# GIP-CCS811.net
KiCad netlist of a schematic drawn in EAGLE
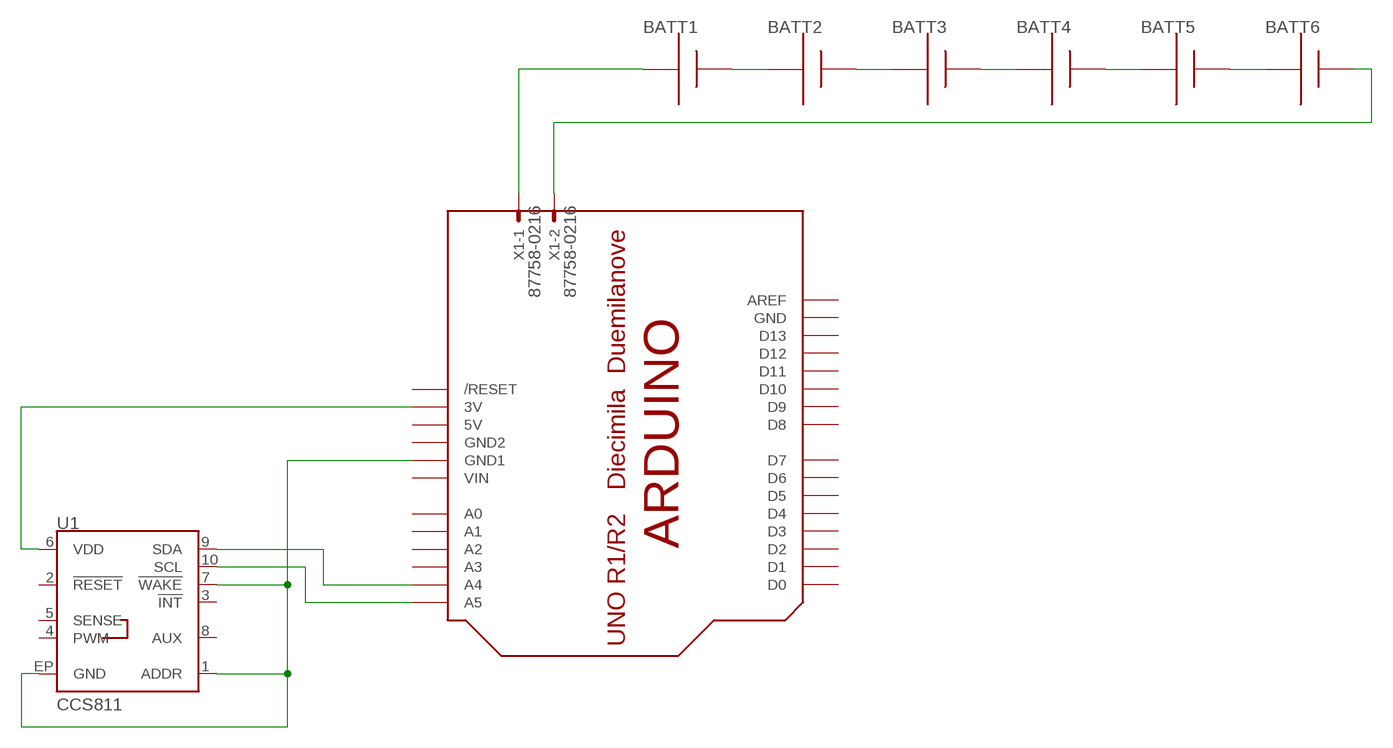
[diagram p0: schematic, sheet 1]

(export (version "E")
  (design (tool "Eeschema 10.0.6"))
  (components
    (comp (ref "BATT1")
      (value "AAA")
      (footprint "eagle-import:12BH412")
      (libsource (lib "eagle-import") (part "AAA"))
    )
    (comp (ref "BATT2")
      (value "AAA")
      (footprint "eagle-import:12BH412")
      (libsource (lib "eagle-import") (part "AAA"))
    )
    (comp (ref "BATT3")
      (value "AAA")
      (footprint "eagle-import:12BH412")
      (libsource (lib "eagle-import") (part "AAA"))
    )
    (comp (ref "BATT4")
      (value "AAA")
      (footprint "eagle-import:12BH412")
      (libsource (lib "eagle-import") (part "AAA"))
    )
    (comp (ref "BATT5")
      (value "AAA")
      (footprint "eagle-import:12BH412")
      (libsource (lib "eagle-import") (part "AAA"))
    )
    (comp (ref "BATT6")
      (value "AAA")
      (footprint "eagle-import:12BH412")
      (libsource (lib "eagle-import") (part "AAA"))
    )
    (comp (ref "U$1")
      (value "ARDUINO-BPLACE")
      (footprint "eagle-import:ARDUINO-BPLACE")
      (libsource (lib "eagle-import") (part "ARDUINO-BPLACE"))
    )
    (comp (ref "U1")
      (value "CCS811")
      (footprint "eagle-import:LGA10")
      (libsource (lib "eagle-import") (part "CCS811"))
    )
    (comp (ref "X1")
      (value "87758-0216")
      (footprint "eagle-import:87758-0216")
      (fields (field (name "MF") "MOLEX"))
      (libsource (lib "eagle-import") (part "87758-0216"))
    )
  )
  (nets
    (net (code "1") (name "/5V") (class "Default")
      (node (ref "U$1") (pin "5V") (pinfunction "5V_5V") (pintype "power_in"))
    )
    (net (code "2") (name "/GND") (class "Default")
      (node (ref "U$1") (pin "GND") (pinfunction "GND_GND") (pintype "power_in"))
    )
    (net (code "3") (name "/GND2") (class "Default")
      (node (ref "U$1") (pin "GND2") (pinfunction "GND2_GND2") (pintype "power_in"))
    )
    (net (code "4") (name "/VIN") (class "Default")
      (node (ref "U$1") (pin "VIN") (pinfunction "VIN_VIN") (pintype "power_in"))
    )
    (net (code "5") (name "Net-(BATT1-Pad+)") (class "Default")
      (node (ref "BATT1") (pin "+") (pinfunction "+_+") (pintype "bidirectional"))
      (node (ref "BATT2") (pin "-") (pinfunction "-_-") (pintype "bidirectional"))
    )
    (net (code "6") (name "Net-(BATT2-Pad+)") (class "Default")
      (node (ref "BATT2") (pin "+") (pinfunction "+_+") (pintype "bidirectional"))
      (node (ref "BATT3") (pin "-") (pinfunction "-_-") (pintype "bidirectional"))
    )
    (net (code "7") (name "Net-(BATT3-Pad+)") (class "Default")
      (node (ref "BATT3") (pin "+") (pinfunction "+_+") (pintype "bidirectional"))
      (node (ref "BATT4") (pin "-") (pinfunction "-_-") (pintype "bidirectional"))
    )
    (net (code "8") (name "Net-(BATT4-Pad+)") (class "Default")
      (node (ref "BATT4") (pin "+") (pinfunction "+_+") (pintype "bidirectional"))
      (node (ref "BATT5") (pin "-") (pinfunction "-_-") (pintype "bidirectional"))
    )
    (net (code "9") (name "Net-(BATT5-Pad+)") (class "Default")
      (node (ref "BATT5") (pin "+") (pinfunction "+_+") (pintype "bidirectional"))
      (node (ref "BATT6") (pin "-") (pinfunction "-_-") (pintype "bidirectional"))
    )
    (net (code "10") (name "Net-(U1-ADDR)") (class "Default")
      (node (ref "U$1") (pin "GND1") (pinfunction "GND1_GND1") (pintype "power_in"))
      (node (ref "U1") (pin "1") (pinfunction "ADDR_1") (pintype "bidirectional"))
      (node (ref "U1") (pin "7") (pinfunction "~{WAKE}_7") (pintype "bidirectional"))
      (node (ref "U1") (pin "EP") (pinfunction "GND_EP") (pintype "bidirectional"))
    )
    (net (code "11") (name "Net-(U1-SCL)") (class "Default")
      (node (ref "U$1") (pin "A5") (pinfunction "A5_A5") (pintype "bidirectional"))
      (node (ref "U1") (pin "10") (pinfunction "SCL_10") (pintype "bidirectional"))
    )
    (net (code "12") (name "Net-(U1-SDA)") (class "Default")
      (node (ref "U$1") (pin "A4") (pinfunction "A4_A4") (pintype "bidirectional"))
      (node (ref "U1") (pin "9") (pinfunction "SDA_9") (pintype "bidirectional"))
    )
    (net (code "13") (name "Net-(U1-VDD)") (class "Default")
      (node (ref "U$1") (pin "3V") (pinfunction "3V_3V") (pintype "power_in"))
      (node (ref "U1") (pin "6") (pinfunction "VDD_6") (pintype "bidirectional"))
    )
    (net (code "14") (name "Net-(X1A-S)") (class "Default")
      (node (ref "BATT1") (pin "-") (pinfunction "-_-") (pintype "bidirectional"))
      (node (ref "X1") (pin "1") (pinfunction "S_1") (pintype "passive"))
    )
    (net (code "15") (name "Net-(X1B-S)") (class "Default")
      (node (ref "BATT6") (pin "+") (pinfunction "+_+") (pintype "bidirectional"))
      (node (ref "X1") (pin "2") (pinfunction "S_2") (pintype "passive"))
    )
    (net (code "16") (name "unconnected-(U$1-PadA0)") (class "Default")
      (node (ref "U$1") (pin "A0") (pinfunction "A0_A0") (pintype "bidirectional"))
    )
    (net (code "17") (name "unconnected-(U$1-PadA1)") (class "Default")
      (node (ref "U$1") (pin "A1") (pinfunction "A1_A1") (pintype "bidirectional"))
    )
    (net (code "18") (name "unconnected-(U$1-PadA2)") (class "Default")
      (node (ref "U$1") (pin "A2") (pinfunction "A2_A2") (pintype "bidirectional"))
    )
    (net (code "19") (name "unconnected-(U$1-PadA3)") (class "Default")
      (node (ref "U$1") (pin "A3") (pinfunction "A3_A3") (pintype "bidirectional"))
    )
    (net (code "20") (name "unconnected-(U$1-PadAREF)") (class "Default")
      (node (ref "U$1") (pin "AREF") (pinfunction "AREF_AREF") (pintype "bidirectional"))
    )
    (net (code "21") (name "unconnected-(U$1-PadD0)") (class "Default")
      (node (ref "U$1") (pin "D0") (pinfunction "D0_D0") (pintype "bidirectional"))
    )
    (net (code "22") (name "unconnected-(U$1-PadD1)") (class "Default")
      (node (ref "U$1") (pin "D1") (pinfunction "D1_D1") (pintype "bidirectional"))
    )
    (net (code "23") (name "unconnected-(U$1-PadD2)") (class "Default")
      (node (ref "U$1") (pin "D2") (pinfunction "D2_D2") (pintype "bidirectional"))
    )
    (net (code "24") (name "unconnected-(U$1-PadD3)") (class "Default")
      (node (ref "U$1") (pin "D3") (pinfunction "D3_D3") (pintype "bidirectional"))
    )
    (net (code "25") (name "unconnected-(U$1-PadD4)") (class "Default")
      (node (ref "U$1") (pin "D4") (pinfunction "D4_D4") (pintype "bidirectional"))
    )
    (net (code "26") (name "unconnected-(U$1-PadD5)") (class "Default")
      (node (ref "U$1") (pin "D5") (pinfunction "D5_D5") (pintype "bidirectional"))
    )
    (net (code "27") (name "unconnected-(U$1-PadD6)") (class "Default")
      (node (ref "U$1") (pin "D6") (pinfunction "D6_D6") (pintype "bidirectional"))
    )
    (net (code "28") (name "unconnected-(U$1-PadD7)") (class "Default")
      (node (ref "U$1") (pin "D7") (pinfunction "D7_D7") (pintype "bidirectional"))
    )
    (net (code "29") (name "unconnected-(U$1-PadD8)") (class "Default")
      (node (ref "U$1") (pin "D8") (pinfunction "D8_D8") (pintype "bidirectional"))
    )
    (net (code "30") (name "unconnected-(U$1-PadD9)") (class "Default")
      (node (ref "U$1") (pin "D9") (pinfunction "D9_D9") (pintype "bidirectional"))
    )
    (net (code "31") (name "unconnected-(U$1-PadD10)") (class "Default")
      (node (ref "U$1") (pin "D10") (pinfunction "D10_D10") (pintype "bidirectional"))
    )
    (net (code "32") (name "unconnected-(U$1-PadD11)") (class "Default")
      (node (ref "U$1") (pin "D11") (pinfunction "D11_D11") (pintype "bidirectional"))
    )
    (net (code "33") (name "unconnected-(U$1-PadD12)") (class "Default")
      (node (ref "U$1") (pin "D12") (pinfunction "D12_D12") (pintype "bidirectional"))
    )
    (net (code "34") (name "unconnected-(U$1-PadD13)") (class "Default")
      (node (ref "U$1") (pin "D13") (pinfunction "D13_D13") (pintype "bidirectional"))
    )
    (net (code "35") (name "unconnected-(U$1-{slash}RESET-PadRESET)") (class "Default")
      (node (ref "U$1") (pin "RESET") (pinfunction "/RESET_RESET") (pintype "bidirectional"))
    )
    (net (code "36") (name "unconnected-(U1-AUX-Pad8)") (class "Default")
      (node (ref "U1") (pin "8") (pinfunction "AUX_8") (pintype "bidirectional"))
    )
    (net (code "37") (name "unconnected-(U1-PWM-Pad4)") (class "Default")
      (node (ref "U1") (pin "4") (pinfunction "PWM_4") (pintype "bidirectional"))
    )
    (net (code "38") (name "unconnected-(U1-SENSE-Pad5)") (class "Default")
      (node (ref "U1") (pin "5") (pinfunction "SENSE_5") (pintype "bidirectional"))
    )
    (net (code "39") (name "unconnected-(U1-~{INT}-Pad3)") (class "Default")
      (node (ref "U1") (pin "3") (pinfunction "~{INT}_3") (pintype "bidirectional"))
    )
    (net (code "40") (name "unconnected-(U1-~{RESET}-Pad2)") (class "Default")
      (node (ref "U1") (pin "2") (pinfunction "~{RESET}_2") (pintype "bidirectional"))
    )
  )
)
